# RectifierPart.net
KiCad netlist of a schematic drawn in EAGLE
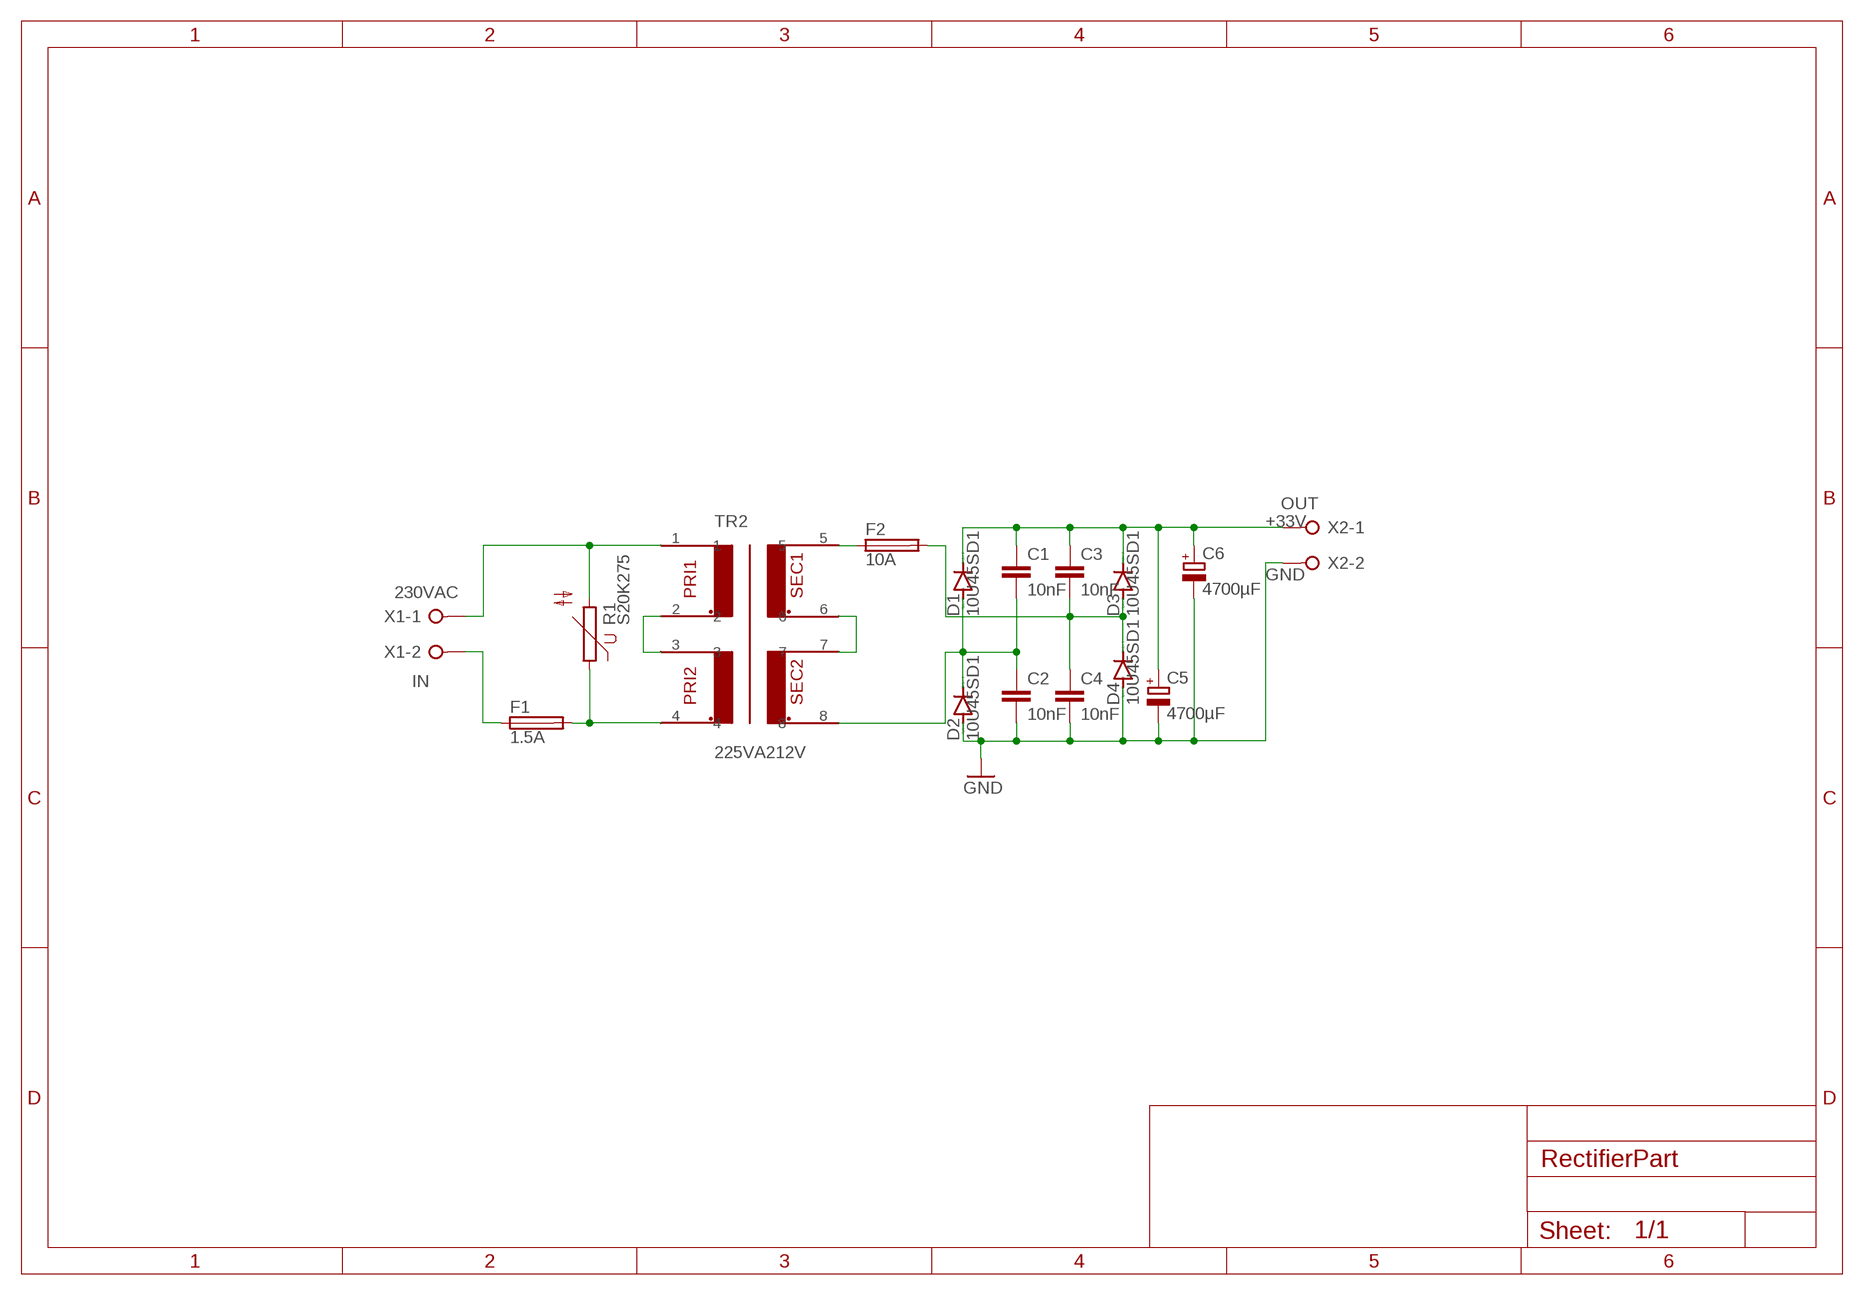
[diagram p0: schematic, sheet 1]

(export (version "E")
  (design (tool "Eeschema 10.0.6"))
  (components
    (comp (ref "C1")
      (value "10nF")
      (footprint "eagle-import:C050-024X044")
      (libsource (lib "eagle-import") (part "C-EU050-024X044"))
    )
    (comp (ref "C2")
      (value "10nF")
      (footprint "eagle-import:C050-024X044")
      (libsource (lib "eagle-import") (part "C-EU050-024X044"))
    )
    (comp (ref "C3")
      (value "10nF")
      (footprint "eagle-import:C050-024X044")
      (libsource (lib "eagle-import") (part "C-EU050-024X044"))
    )
    (comp (ref "C4")
      (value "10nF")
      (footprint "eagle-import:C050-024X044")
      (libsource (lib "eagle-import") (part "C-EU050-024X044"))
    )
    (comp (ref "C5")
      (value "4700µF")
      (footprint "eagle-import:E5-13")
      (libsource (lib "eagle-import") (part "CPOL-EUE5-13"))
    )
    (comp (ref "C6")
      (value "4700µF")
      (footprint "eagle-import:E5-13")
      (libsource (lib "eagle-import") (part "CPOL-EUE5-13"))
    )
    (comp (ref "D1")
      (value "10U45SD1")
      (footprint "eagle-import:DO201-15")
      (libsource (lib "eagle-import") (part "1N5400"))
    )
    (comp (ref "D2")
      (value "10U45SD1")
      (footprint "eagle-import:DO201-15")
      (libsource (lib "eagle-import") (part "1N5400"))
    )
    (comp (ref "D3")
      (value "10U45SD1")
      (footprint "eagle-import:DO201-15")
      (libsource (lib "eagle-import") (part "1N5400"))
    )
    (comp (ref "D4")
      (value "10U45SD1")
      (footprint "eagle-import:DO201-15")
      (libsource (lib "eagle-import") (part "1N5400"))
    )
    (comp (ref "F1")
      (value "1.5A")
      (footprint "eagle-import:SH22,5")
      (fields (field (name "MF") "SCHURTER") (field (name "MPN") "0031.8201"))
      (libsource (lib "eagle-import") (part "SH22,5"))
    )
    (comp (ref "F2")
      (value "10A")
      (footprint "eagle-import:SH22,5")
      (fields (field (name "MF") "SCHURTER") (field (name "MPN") "0031.8201"))
      (libsource (lib "eagle-import") (part "SH22,5"))
    )
    (comp (ref "R1")
      (value "S20K275")
      (footprint "eagle-import:S20K275")
      (libsource (lib "eagle-import") (part "S20K275"))
    )
    (comp (ref "TR2")
      (value "225VA212V")
      (footprint "eagle-import:RKD225-2X12")
      (libsource (lib "eagle-import") (part "225VA212V"))
    )
    (comp (ref "X1")
      (value "IN")
      (footprint "eagle-import:W237-132")
      (libsource (lib "eagle-import") (part "W237-02P"))
    )
    (comp (ref "X2")
      (value "OUT")
      (footprint "eagle-import:W237-132")
      (libsource (lib "eagle-import") (part "W237-02P"))
    )
  )
  (nets
    (net (code "1") (name "/+33V") (class "Default")
      (node (ref "C1") (pin "1") (pinfunction "1_1") (pintype "passive"))
      (node (ref "C3") (pin "1") (pinfunction "1_1") (pintype "passive"))
      (node (ref "C5") (pin "+") (pinfunction "+_+") (pintype "passive"))
      (node (ref "C6") (pin "+") (pinfunction "+_+") (pintype "passive"))
      (node (ref "D1") (pin "C") (pinfunction "C_C") (pintype "passive"))
      (node (ref "D3") (pin "C") (pinfunction "C_C") (pintype "passive"))
      (node (ref "X2") (pin "1") (pinfunction "KL_1") (pintype "passive"))
    )
    (net (code "2") (name "/230VAC") (class "Default")
      (node (ref "R1") (pin "2") (pinfunction "2_2") (pintype "passive"))
      (node (ref "TR2") (pin "1") (pinfunction "1_1") (pintype "bidirectional"))
      (node (ref "X1") (pin "1") (pinfunction "KL_1") (pintype "passive"))
    )
    (net (code "3") (name "GND") (class "Default")
      (node (ref "C2") (pin "2") (pinfunction "2_2") (pintype "passive"))
      (node (ref "C4") (pin "2") (pinfunction "2_2") (pintype "passive"))
      (node (ref "C5") (pin "-") (pinfunction "-_-") (pintype "passive"))
      (node (ref "C6") (pin "-") (pinfunction "-_-") (pintype "passive"))
      (node (ref "D2") (pin "A") (pinfunction "A_A") (pintype "passive"))
      (node (ref "D4") (pin "A") (pinfunction "A_A") (pintype "passive"))
      (node (ref "X2") (pin "2") (pinfunction "KL_2") (pintype "passive"))
    )
    (net (code "4") (name "Net-(C1-Pad2)") (class "Default")
      (node (ref "C1") (pin "2") (pinfunction "2_2") (pintype "passive"))
      (node (ref "C2") (pin "1") (pinfunction "1_1") (pintype "passive"))
      (node (ref "D1") (pin "A") (pinfunction "A_A") (pintype "passive"))
      (node (ref "D2") (pin "C") (pinfunction "C_C") (pintype "passive"))
      (node (ref "TR2") (pin "8") (pinfunction "8_8") (pintype "bidirectional"))
    )
    (net (code "5") (name "Net-(C3-Pad2)") (class "Default")
      (node (ref "C3") (pin "2") (pinfunction "2_2") (pintype "passive"))
      (node (ref "C4") (pin "1") (pinfunction "1_1") (pintype "passive"))
      (node (ref "D3") (pin "A") (pinfunction "A_A") (pintype "passive"))
      (node (ref "D4") (pin "C") (pinfunction "C_C") (pintype "passive"))
      (node (ref "F2") (pin "2") (pinfunction "2_2") (pintype "passive"))
    )
    (net (code "6") (name "Net-(F1-Pad2)") (class "Default")
      (node (ref "F1") (pin "2") (pinfunction "2_2") (pintype "passive"))
      (node (ref "R1") (pin "1") (pinfunction "1_1") (pintype "passive"))
      (node (ref "TR2") (pin "4") (pinfunction "4_4") (pintype "bidirectional"))
    )
    (net (code "7") (name "Net-(F2-Pad1)") (class "Default")
      (node (ref "F2") (pin "1") (pinfunction "1_1") (pintype "passive"))
      (node (ref "TR2") (pin "5") (pinfunction "5_5") (pintype "bidirectional"))
    )
    (net (code "8") (name "Net-(TR2-Pad2)") (class "Default")
      (node (ref "TR2") (pin "2") (pinfunction "2_2") (pintype "bidirectional"))
      (node (ref "TR2") (pin "3") (pinfunction "3_3") (pintype "bidirectional"))
    )
    (net (code "9") (name "Net-(TR2-Pad6)") (class "Default")
      (node (ref "TR2") (pin "6") (pinfunction "6_6") (pintype "bidirectional"))
      (node (ref "TR2") (pin "7") (pinfunction "7_7") (pintype "bidirectional"))
    )
    (net (code "10") (name "Net-(X1B-KL)") (class "Default")
      (node (ref "F1") (pin "1") (pinfunction "1_1") (pintype "passive"))
      (node (ref "X1") (pin "2") (pinfunction "KL_2") (pintype "passive"))
    )
  )
)
